# imsensor-esp-v01.net
KiCad netlist of a schematic drawn in EAGLE
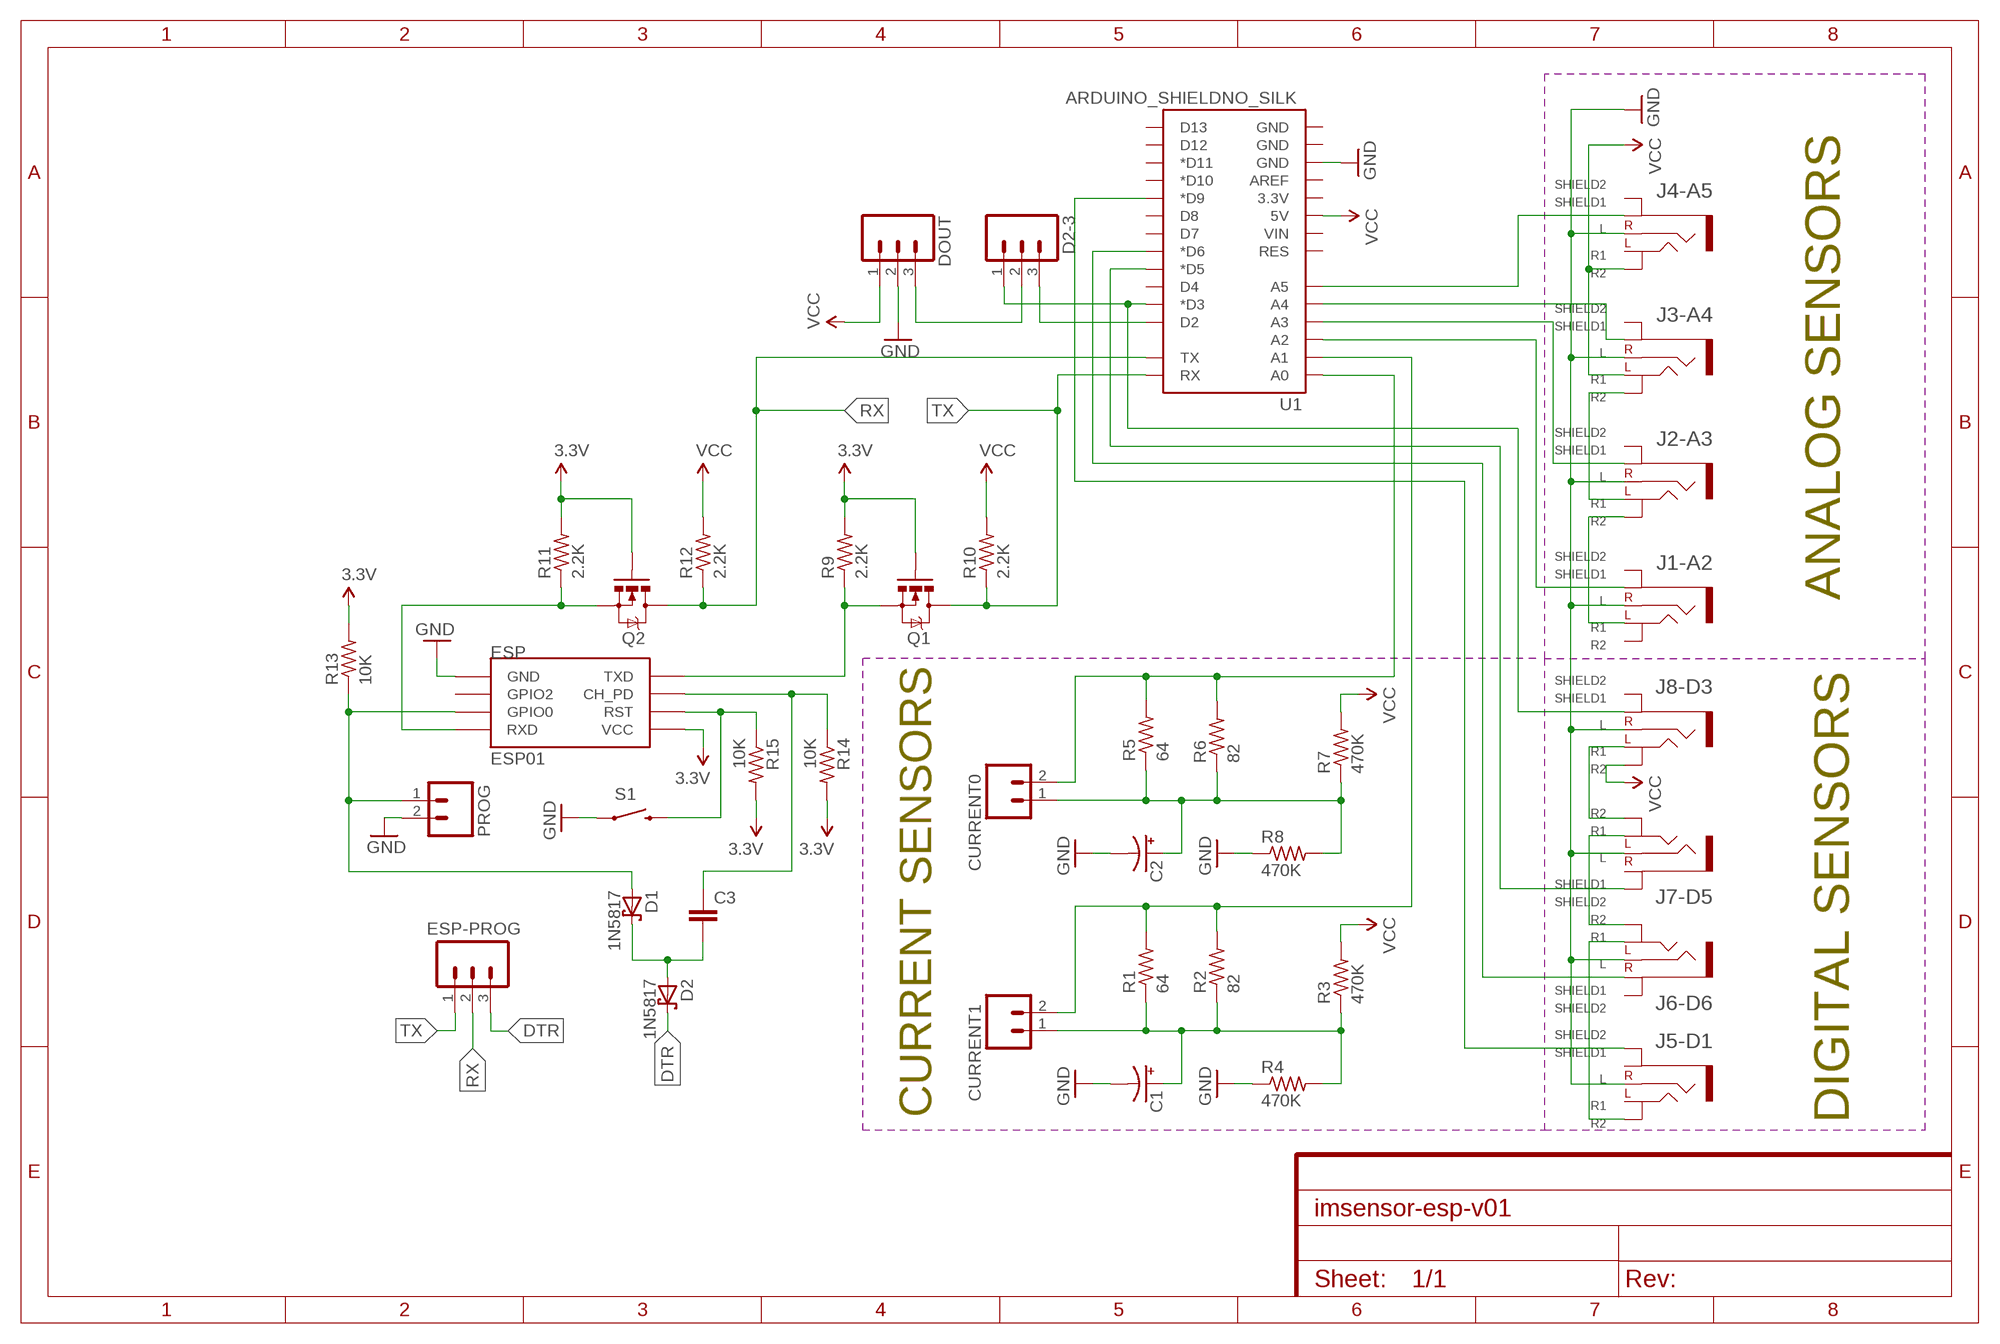
[diagram p0: schematic, sheet 1]

(export (version "E")
  (design (tool "Eeschema 10.0.6"))
  (components
    (comp (ref "C1")
      (value "10UF-25V-20%(PTH)")
      (footprint "eagle-import:CPOL-RADIAL-10UF-25V")
      (libsource (lib "eagle-import") (part "10UF-25V-20%(PTH)"))
    )
    (comp (ref "C2")
      (value "10UF-25V-20%(PTH)")
      (footprint "eagle-import:CPOL-RADIAL-10UF-25V")
      (libsource (lib "eagle-import") (part "10UF-25V-20%(PTH)"))
    )
    (comp (ref "C3")
      (value "CAPPTH")
      (footprint "eagle-import:CAP-PTH-SMALL")
      (libsource (lib "eagle-import") (part "CAPPTH"))
    )
    (comp (ref "CURRENT0")
      (value "M02PTH")
      (footprint "eagle-import:1X02")
      (libsource (lib "eagle-import") (part "M02PTH"))
    )
    (comp (ref "CURRENT1")
      (value "M02PTH")
      (footprint "eagle-import:1X02")
      (libsource (lib "eagle-import") (part "M02PTH"))
    )
    (comp (ref "D1")
      (value "1N5817")
      (footprint "eagle-import:DO35-7")
      (libsource (lib "eagle-import") (part "SCHOTTKY-DIODEDO35-7"))
    )
    (comp (ref "D2")
      (value "1N5817")
      (footprint "eagle-import:DO35-7")
      (libsource (lib "eagle-import") (part "SCHOTTKY-DIODEDO35-7"))
    )
    (comp (ref "D2-3")
      (value "M03PTH")
      (footprint "eagle-import:1X03")
      (libsource (lib "eagle-import") (part "M03PTH"))
    )
    (comp (ref "DOUT")
      (value "M03PTH")
      (footprint "eagle-import:1X03")
      (libsource (lib "eagle-import") (part "M03PTH"))
    )
    (comp (ref "ESP")
      (value "ESP01")
      (footprint "eagle-import:ESP01")
      (libsource (lib "eagle-import") (part "ESP01"))
    )
    (comp (ref "ESP-PROG")
      (value "M03PTH")
      (footprint "eagle-import:1X03")
      (libsource (lib "eagle-import") (part "M03PTH"))
    )
    (comp (ref "J1-A2")
      (value "PJ-313-SPAD")
      (footprint "eagle-import:PJ-313-5PIN-SMALL")
      (libsource (lib "eagle-import") (part "PJ-313-SPAD"))
    )
    (comp (ref "J2-A3")
      (value "PJ-313-SPAD")
      (footprint "eagle-import:PJ-313-5PIN-SMALL")
      (libsource (lib "eagle-import") (part "PJ-313-SPAD"))
    )
    (comp (ref "J3-A4")
      (value "PJ-313-SPAD")
      (footprint "eagle-import:PJ-313-5PIN-SMALL")
      (libsource (lib "eagle-import") (part "PJ-313-SPAD"))
    )
    (comp (ref "J4-A5")
      (value "PJ-313-SPAD")
      (footprint "eagle-import:PJ-313-5PIN-SMALL")
      (libsource (lib "eagle-import") (part "PJ-313-SPAD"))
    )
    (comp (ref "J5-D1")
      (value "PJ-313-SPAD")
      (footprint "eagle-import:PJ-313-5PIN-SMALL")
      (libsource (lib "eagle-import") (part "PJ-313-SPAD"))
    )
    (comp (ref "J6-D6")
      (value "PJ-313-SPAD")
      (footprint "eagle-import:PJ-313-5PIN-SMALL")
      (libsource (lib "eagle-import") (part "PJ-313-SPAD"))
    )
    (comp (ref "J7-D5")
      (value "PJ-313-SPAD")
      (footprint "eagle-import:PJ-313-5PIN-SMALL")
      (libsource (lib "eagle-import") (part "PJ-313-SPAD"))
    )
    (comp (ref "J8-D3")
      (value "PJ-313-SPAD")
      (footprint "eagle-import:PJ-313-5PIN-SMALL")
      (libsource (lib "eagle-import") (part "PJ-313-SPAD"))
    )
    (comp (ref "PROG")
      (value "M02PTH")
      (footprint "eagle-import:1X02")
      (libsource (lib "eagle-import") (part "M02PTH"))
    )
    (comp (ref "Q1")
      (value "MOSFET-NCHANNEL2N7000")
      (footprint "eagle-import:TO-92")
      (libsource (lib "eagle-import") (part "MOSFET-NCHANNEL2N7000"))
    )
    (comp (ref "Q2")
      (value "MOSFET-NCHANNEL2N7000")
      (footprint "eagle-import:TO-92")
      (libsource (lib "eagle-import") (part "MOSFET-NCHANNEL2N7000"))
    )
    (comp (ref "R1")
      (value "64")
      (footprint "eagle-import:0207_10")
      (libsource (lib "eagle-import") (part "R-US_0207/10"))
    )
    (comp (ref "R2")
      (value "82")
      (footprint "eagle-import:0207_10")
      (libsource (lib "eagle-import") (part "R-US_0207/10"))
    )
    (comp (ref "R3")
      (value "470K")
      (footprint "eagle-import:0207_10")
      (libsource (lib "eagle-import") (part "R-US_0207/10"))
    )
    (comp (ref "R4")
      (value "470K")
      (footprint "eagle-import:0207_10")
      (libsource (lib "eagle-import") (part "R-US_0207/10"))
    )
    (comp (ref "R5")
      (value "64")
      (footprint "eagle-import:0207_10")
      (libsource (lib "eagle-import") (part "R-US_0207/10"))
    )
    (comp (ref "R6")
      (value "82")
      (footprint "eagle-import:0207_10")
      (libsource (lib "eagle-import") (part "R-US_0207/10"))
    )
    (comp (ref "R7")
      (value "470K")
      (footprint "eagle-import:0207_10")
      (libsource (lib "eagle-import") (part "R-US_0207/10"))
    )
    (comp (ref "R8")
      (value "470K")
      (footprint "eagle-import:0207_10")
      (libsource (lib "eagle-import") (part "R-US_0207/10"))
    )
    (comp (ref "R9")
      (value "2.2K")
      (footprint "eagle-import:0207_10")
      (libsource (lib "eagle-import") (part "R-US_0207/10"))
    )
    (comp (ref "R10")
      (value "2.2K")
      (footprint "eagle-import:0207_10")
      (libsource (lib "eagle-import") (part "R-US_0207/10"))
    )
    (comp (ref "R11")
      (value "2.2K")
      (footprint "eagle-import:0207_10")
      (libsource (lib "eagle-import") (part "R-US_0207/10"))
    )
    (comp (ref "R12")
      (value "2.2K")
      (footprint "eagle-import:0207_10")
      (libsource (lib "eagle-import") (part "R-US_0207/10"))
    )
    (comp (ref "R13")
      (value "10K")
      (footprint "eagle-import:0207_10")
      (libsource (lib "eagle-import") (part "R-US_0207/10"))
    )
    (comp (ref "R14")
      (value "10K")
      (footprint "eagle-import:0207_10")
      (libsource (lib "eagle-import") (part "R-US_0207/10"))
    )
    (comp (ref "R15")
      (value "10K")
      (footprint "eagle-import:0207_10")
      (libsource (lib "eagle-import") (part "R-US_0207/10"))
    )
    (comp (ref "S1")
      (value "SWITCH-MOMENTARY-2PTH")
      (footprint "eagle-import:TACTILE-PTH")
      (libsource (lib "eagle-import") (part "SWITCH-MOMENTARY-2PTH"))
    )
    (comp (ref "U1")
      (value "ARDUINO_SHIELDNO_SILK")
      (footprint "eagle-import:DUEMILANOVE_VIAS")
      (libsource (lib "eagle-import") (part "ARDUINO_SHIELDNO_SILK"))
    )
  )
  (nets
    (net (code "1") (name "3.3V") (class "Default")
      (node (ref "ESP") (pin "VCC") (pinfunction "VCC_VCC") (pintype "bidirectional"))
      (node (ref "Q1") (pin "2") (pinfunction "G_2") (pintype "passive"))
      (node (ref "Q2") (pin "2") (pinfunction "G_2") (pintype "passive"))
      (node (ref "R11") (pin "2") (pinfunction "2_2") (pintype "passive"))
      (node (ref "R13") (pin "2") (pinfunction "2_2") (pintype "passive"))
      (node (ref "R14") (pin "2") (pinfunction "2_2") (pintype "passive"))
      (node (ref "R15") (pin "2") (pinfunction "2_2") (pintype "passive"))
      (node (ref "R9") (pin "2") (pinfunction "2_2") (pintype "passive"))
    )
    (net (code "2") (name "DTR") (class "Default")
      (node (ref "D2") (pin "C") (pinfunction "C_C") (pintype "passive"))
      (node (ref "ESP-PROG") (pin "3") (pinfunction "3_3") (pintype "passive"))
    )
    (net (code "3") (name "GND") (class "Default")
      (node (ref "C1") (pin "2") (pinfunction "-_2") (pintype "passive"))
      (node (ref "C2") (pin "2") (pinfunction "-_2") (pintype "passive"))
      (node (ref "DOUT") (pin "2") (pinfunction "2_2") (pintype "passive"))
      (node (ref "ESP") (pin "GND") (pinfunction "GND_GND") (pintype "bidirectional"))
      (node (ref "J1-A2") (pin "2") (pinfunction "R_2") (pintype "bidirectional"))
      (node (ref "J2-A3") (pin "2") (pinfunction "R_2") (pintype "bidirectional"))
      (node (ref "J3-A4") (pin "2") (pinfunction "R_2") (pintype "bidirectional"))
      (node (ref "J4-A5") (pin "2") (pinfunction "R_2") (pintype "bidirectional"))
      (node (ref "J5-D1") (pin "2") (pinfunction "R_2") (pintype "bidirectional"))
      (node (ref "J6-D6") (pin "2") (pinfunction "R_2") (pintype "bidirectional"))
      (node (ref "J7-D5") (pin "2") (pinfunction "R_2") (pintype "bidirectional"))
      (node (ref "J8-D3") (pin "2") (pinfunction "R_2") (pintype "bidirectional"))
      (node (ref "PROG") (pin "2") (pinfunction "2_2") (pintype "passive"))
      (node (ref "R4") (pin "1") (pinfunction "1_1") (pintype "passive"))
      (node (ref "R8") (pin "1") (pinfunction "1_1") (pintype "passive"))
      (node (ref "S1") (pin "1") (pinfunction "1_1") (pintype "passive"))
      (node (ref "U1") (pin "GND@2") (pinfunction "GND_GND@2") (pintype "bidirectional"))
    )
    (net (code "4") (name "Net-(C1-+)") (class "Default")
      (node (ref "C1") (pin "1") (pinfunction "+_1") (pintype "passive"))
      (node (ref "CURRENT1") (pin "1") (pinfunction "1_1") (pintype "passive"))
      (node (ref "R1") (pin "1") (pinfunction "1_1") (pintype "passive"))
      (node (ref "R2") (pin "1") (pinfunction "1_1") (pintype "passive"))
      (node (ref "R3") (pin "1") (pinfunction "1_1") (pintype "passive"))
      (node (ref "R4") (pin "2") (pinfunction "2_2") (pintype "passive"))
    )
    (net (code "5") (name "Net-(C2-+)") (class "Default")
      (node (ref "C2") (pin "1") (pinfunction "+_1") (pintype "passive"))
      (node (ref "CURRENT0") (pin "1") (pinfunction "1_1") (pintype "passive"))
      (node (ref "R5") (pin "1") (pinfunction "1_1") (pintype "passive"))
      (node (ref "R6") (pin "1") (pinfunction "1_1") (pintype "passive"))
      (node (ref "R7") (pin "1") (pinfunction "1_1") (pintype "passive"))
      (node (ref "R8") (pin "2") (pinfunction "2_2") (pintype "passive"))
    )
    (net (code "6") (name "Net-(C3-Pad1)") (class "Default")
      (node (ref "C3") (pin "1") (pinfunction "1_1") (pintype "passive"))
      (node (ref "ESP") (pin "CH_PD") (pinfunction "CH_PD_CH_PD") (pintype "bidirectional"))
      (node (ref "R14") (pin "1") (pinfunction "1_1") (pintype "passive"))
    )
    (net (code "7") (name "Net-(C3-Pad2)") (class "Default")
      (node (ref "C3") (pin "2") (pinfunction "2_2") (pintype "passive"))
      (node (ref "D1") (pin "C") (pinfunction "C_C") (pintype "passive"))
      (node (ref "D2") (pin "A") (pinfunction "A_A") (pintype "passive"))
    )
    (net (code "8") (name "Net-(CURRENT0-Pad2)") (class "Default")
      (node (ref "CURRENT0") (pin "2") (pinfunction "2_2") (pintype "passive"))
      (node (ref "R5") (pin "2") (pinfunction "2_2") (pintype "passive"))
      (node (ref "R6") (pin "2") (pinfunction "2_2") (pintype "passive"))
      (node (ref "U1") (pin "A0") (pinfunction "A0_A0") (pintype "bidirectional"))
    )
    (net (code "9") (name "Net-(CURRENT1-Pad2)") (class "Default")
      (node (ref "CURRENT1") (pin "2") (pinfunction "2_2") (pintype "passive"))
      (node (ref "R1") (pin "2") (pinfunction "2_2") (pintype "passive"))
      (node (ref "R2") (pin "2") (pinfunction "2_2") (pintype "passive"))
      (node (ref "U1") (pin "A1") (pinfunction "A1_A1") (pintype "bidirectional"))
    )
    (net (code "10") (name "Net-(D1-PadA)") (class "Default")
      (node (ref "D1") (pin "A") (pinfunction "A_A") (pintype "passive"))
      (node (ref "ESP") (pin "GPIO0") (pinfunction "GPIO0_GPIO0") (pintype "bidirectional"))
      (node (ref "PROG") (pin "1") (pinfunction "1_1") (pintype "passive"))
      (node (ref "R13") (pin "1") (pinfunction "1_1") (pintype "passive"))
    )
    (net (code "11") (name "Net-(D2-3-Pad2)") (class "Default")
      (node (ref "D2-3") (pin "2") (pinfunction "2_2") (pintype "passive"))
      (node (ref "DOUT") (pin "3") (pinfunction "3_3") (pintype "passive"))
    )
    (net (code "12") (name "Net-(D2-3-Pad3)") (class "Default")
      (node (ref "D2-3") (pin "3") (pinfunction "3_3") (pintype "passive"))
      (node (ref "U1") (pin "D2") (pinfunction "D2_D2") (pintype "bidirectional"))
    )
    (net (code "13") (name "Net-(ESP-RXD)") (class "Default")
      (node (ref "ESP") (pin "RX") (pinfunction "RXD_RX") (pintype "bidirectional"))
      (node (ref "Q2") (pin "1") (pinfunction "S_1") (pintype "passive"))
      (node (ref "R11") (pin "1") (pinfunction "1_1") (pintype "passive"))
    )
    (net (code "14") (name "Net-(ESP-TXD)") (class "Default")
      (node (ref "ESP") (pin "TX") (pinfunction "TXD_TX") (pintype "bidirectional"))
      (node (ref "Q1") (pin "1") (pinfunction "S_1") (pintype "passive"))
      (node (ref "R9") (pin "1") (pinfunction "1_1") (pintype "passive"))
    )
    (net (code "15") (name "Net-(J1-A2-L1)") (class "Default")
      (node (ref "J1-A2") (pin "3.1") (pinfunction "L1_3.1") (pintype "bidirectional"))
      (node (ref "J2-A3") (pin "3.2") (pinfunction "L2_3.2") (pintype "bidirectional"))
    )
    (net (code "16") (name "Net-(J1-A2-SHIELD1)") (class "Default")
      (node (ref "J1-A2") (pin "1.1") (pinfunction "SHIELD1_1.1") (pintype "bidirectional"))
      (node (ref "U1") (pin "A2") (pinfunction "A2_A2") (pintype "bidirectional"))
    )
    (net (code "17") (name "Net-(J2-A3-L1)") (class "Default")
      (node (ref "J2-A3") (pin "3.1") (pinfunction "L1_3.1") (pintype "bidirectional"))
      (node (ref "J3-A4") (pin "3.2") (pinfunction "L2_3.2") (pintype "bidirectional"))
    )
    (net (code "18") (name "Net-(J2-A3-SHIELD1)") (class "Default")
      (node (ref "J2-A3") (pin "1.1") (pinfunction "SHIELD1_1.1") (pintype "bidirectional"))
      (node (ref "U1") (pin "A3") (pinfunction "A3_A3") (pintype "bidirectional"))
    )
    (net (code "19") (name "Net-(J3-A4-SHIELD1)") (class "Default")
      (node (ref "J3-A4") (pin "1.1") (pinfunction "SHIELD1_1.1") (pintype "bidirectional"))
      (node (ref "U1") (pin "A4") (pinfunction "A4_A4") (pintype "bidirectional"))
    )
    (net (code "20") (name "Net-(J4-A5-SHIELD1)") (class "Default")
      (node (ref "J4-A5") (pin "1.1") (pinfunction "SHIELD1_1.1") (pintype "bidirectional"))
      (node (ref "U1") (pin "A5") (pinfunction "A5_A5") (pintype "bidirectional"))
    )
    (net (code "21") (name "Net-(J5-D1-L2)") (class "Default")
      (node (ref "J5-D1") (pin "3.2") (pinfunction "L2_3.2") (pintype "bidirectional"))
      (node (ref "J6-D6") (pin "3.1") (pinfunction "L1_3.1") (pintype "bidirectional"))
    )
    (net (code "22") (name "Net-(J5-D1-SHIELD2)") (class "Default")
      (node (ref "J5-D1") (pin "1.2") (pinfunction "SHIELD2_1.2") (pintype "bidirectional"))
      (node (ref "U1") (pin "D9") (pinfunction "*D9_D9") (pintype "bidirectional"))
    )
    (net (code "23") (name "Net-(J6-D6-L2)") (class "Default")
      (node (ref "J6-D6") (pin "3.2") (pinfunction "L2_3.2") (pintype "bidirectional"))
      (node (ref "J7-D5") (pin "3.1") (pinfunction "L1_3.1") (pintype "bidirectional"))
    )
    (net (code "24") (name "Net-(J6-D6-SHIELD1)") (class "Default")
      (node (ref "J6-D6") (pin "1.1") (pinfunction "SHIELD1_1.1") (pintype "bidirectional"))
      (node (ref "U1") (pin "D6") (pinfunction "*D6_D6") (pintype "bidirectional"))
    )
    (net (code "25") (name "Net-(J7-D5-L2)") (class "Default")
      (node (ref "J7-D5") (pin "3.2") (pinfunction "L2_3.2") (pintype "bidirectional"))
      (node (ref "J8-D3") (pin "3.1") (pinfunction "L1_3.1") (pintype "bidirectional"))
    )
    (net (code "26") (name "Net-(J7-D5-SHIELD2)") (class "Default")
      (node (ref "J7-D5") (pin "1.2") (pinfunction "SHIELD2_1.2") (pintype "bidirectional"))
      (node (ref "U1") (pin "D5") (pinfunction "*D5_D5") (pintype "bidirectional"))
    )
    (net (code "27") (name "Net-(J8-D3-SHIELD1)") (class "Default")
      (node (ref "D2-3") (pin "1") (pinfunction "1_1") (pintype "passive"))
      (node (ref "J8-D3") (pin "1.1") (pinfunction "SHIELD1_1.1") (pintype "bidirectional"))
      (node (ref "U1") (pin "D3") (pinfunction "*D3_D3") (pintype "bidirectional"))
    )
    (net (code "28") (name "Net-(S1-2)") (class "Default")
      (node (ref "ESP") (pin "RST") (pinfunction "RST_RST") (pintype "bidirectional"))
      (node (ref "R15") (pin "1") (pinfunction "1_1") (pintype "passive"))
      (node (ref "S1") (pin "3") (pinfunction "2_3") (pintype "passive"))
    )
    (net (code "29") (name "RX") (class "Default")
      (node (ref "ESP-PROG") (pin "2") (pinfunction "2_2") (pintype "passive"))
      (node (ref "Q2") (pin "3") (pinfunction "D_3") (pintype "passive"))
      (node (ref "R12") (pin "1") (pinfunction "1_1") (pintype "passive"))
      (node (ref "U1") (pin "TX") (pinfunction "TX_TX") (pintype "bidirectional"))
    )
    (net (code "30") (name "TX") (class "Default")
      (node (ref "ESP-PROG") (pin "1") (pinfunction "1_1") (pintype "passive"))
      (node (ref "Q1") (pin "3") (pinfunction "D_3") (pintype "passive"))
      (node (ref "R10") (pin "1") (pinfunction "1_1") (pintype "passive"))
      (node (ref "U1") (pin "RX") (pinfunction "RX_RX") (pintype "bidirectional"))
    )
    (net (code "31") (name "VCC") (class "Default")
      (node (ref "DOUT") (pin "1") (pinfunction "1_1") (pintype "passive"))
      (node (ref "J3-A4") (pin "3.1") (pinfunction "L1_3.1") (pintype "bidirectional"))
      (node (ref "J4-A5") (pin "3.2") (pinfunction "L2_3.2") (pintype "bidirectional"))
      (node (ref "J8-D3") (pin "3.2") (pinfunction "L2_3.2") (pintype "bidirectional"))
      (node (ref "R10") (pin "2") (pinfunction "2_2") (pintype "passive"))
      (node (ref "R12") (pin "2") (pinfunction "2_2") (pintype "passive"))
      (node (ref "R3") (pin "2") (pinfunction "2_2") (pintype "passive"))
      (node (ref "R7") (pin "2") (pinfunction "2_2") (pintype "passive"))
      (node (ref "U1") (pin "5V") (pinfunction "5V_5V") (pintype "bidirectional"))
    )
    (net (code "32") (name "unconnected-(ESP-PadGPIO2)") (class "Default")
      (node (ref "ESP") (pin "GPIO2") (pinfunction "GPIO2_GPIO2") (pintype "bidirectional"))
    )
    (net (code "33") (name "unconnected-(J1-A2-L2-Pad3.2)") (class "Default")
      (node (ref "J1-A2") (pin "3.2") (pinfunction "L2_3.2") (pintype "bidirectional"))
    )
    (net (code "34") (name "unconnected-(J1-A2-SHIELD2-Pad1.2)") (class "Default")
      (node (ref "J1-A2") (pin "1.2") (pinfunction "SHIELD2_1.2") (pintype "bidirectional"))
    )
    (net (code "35") (name "unconnected-(J2-A3-SHIELD2-Pad1.2)") (class "Default")
      (node (ref "J2-A3") (pin "1.2") (pinfunction "SHIELD2_1.2") (pintype "bidirectional"))
    )
    (net (code "36") (name "unconnected-(J3-A4-SHIELD2-Pad1.2)") (class "Default")
      (node (ref "J3-A4") (pin "1.2") (pinfunction "SHIELD2_1.2") (pintype "bidirectional"))
    )
    (net (code "37") (name "unconnected-(J4-A5-L1-Pad3.1)") (class "Default")
      (node (ref "J4-A5") (pin "3.1") (pinfunction "L1_3.1") (pintype "bidirectional"))
    )
    (net (code "38") (name "unconnected-(J4-A5-SHIELD2-Pad1.2)") (class "Default")
      (node (ref "J4-A5") (pin "1.2") (pinfunction "SHIELD2_1.2") (pintype "bidirectional"))
    )
    (net (code "39") (name "unconnected-(J5-D1-L1-Pad3.1)") (class "Default")
      (node (ref "J5-D1") (pin "3.1") (pinfunction "L1_3.1") (pintype "bidirectional"))
    )
    (net (code "40") (name "unconnected-(J5-D1-SHIELD1-Pad1.1)") (class "Default")
      (node (ref "J5-D1") (pin "1.1") (pinfunction "SHIELD1_1.1") (pintype "bidirectional"))
    )
    (net (code "41") (name "unconnected-(J6-D6-SHIELD2-Pad1.2)") (class "Default")
      (node (ref "J6-D6") (pin "1.2") (pinfunction "SHIELD2_1.2") (pintype "bidirectional"))
    )
    (net (code "42") (name "unconnected-(J7-D5-SHIELD1-Pad1.1)") (class "Default")
      (node (ref "J7-D5") (pin "1.1") (pinfunction "SHIELD1_1.1") (pintype "bidirectional"))
    )
    (net (code "43") (name "unconnected-(J8-D3-SHIELD2-Pad1.2)") (class "Default")
      (node (ref "J8-D3") (pin "1.2") (pinfunction "SHIELD2_1.2") (pintype "bidirectional"))
    )
    (net (code "44") (name "unconnected-(U1-*D10-PadD10)") (class "Default")
      (node (ref "U1") (pin "D10") (pinfunction "*D10_D10") (pintype "bidirectional"))
    )
    (net (code "45") (name "unconnected-(U1-*D11-PadD11)") (class "Default")
      (node (ref "U1") (pin "D11") (pinfunction "*D11_D11") (pintype "bidirectional"))
    )
    (net (code "46") (name "unconnected-(U1-GND-PadGND@0)") (class "Default")
      (node (ref "U1") (pin "GND@0") (pinfunction "GND_GND@0") (pintype "bidirectional"))
    )
    (net (code "47") (name "unconnected-(U1-GND-PadGND@1)") (class "Default")
      (node (ref "U1") (pin "GND@1") (pinfunction "GND_GND@1") (pintype "bidirectional"))
    )
    (net (code "48") (name "unconnected-(U1-Pad3.3V)") (class "Default")
      (node (ref "U1") (pin "3.3V") (pinfunction "3.3V_3.3V") (pintype "bidirectional"))
    )
    (net (code "49") (name "unconnected-(U1-PadAREF)") (class "Default")
      (node (ref "U1") (pin "AREF") (pinfunction "AREF_AREF") (pintype "bidirectional"))
    )
    (net (code "50") (name "unconnected-(U1-PadD4)") (class "Default")
      (node (ref "U1") (pin "D4") (pinfunction "D4_D4") (pintype "bidirectional"))
    )
    (net (code "51") (name "unconnected-(U1-PadD7)") (class "Default")
      (node (ref "U1") (pin "D7") (pinfunction "D7_D7") (pintype "bidirectional"))
    )
    (net (code "52") (name "unconnected-(U1-PadD8)") (class "Default")
      (node (ref "U1") (pin "D8") (pinfunction "D8_D8") (pintype "bidirectional"))
    )
    (net (code "53") (name "unconnected-(U1-PadD12)") (class "Default")
      (node (ref "U1") (pin "D12") (pinfunction "D12_D12") (pintype "bidirectional"))
    )
    (net (code "54") (name "unconnected-(U1-PadD13)") (class "Default")
      (node (ref "U1") (pin "D13") (pinfunction "D13_D13") (pintype "bidirectional"))
    )
    (net (code "55") (name "unconnected-(U1-PadRES)") (class "Default")
      (node (ref "U1") (pin "RES") (pinfunction "RES_RES") (pintype "bidirectional"))
    )
    (net (code "56") (name "unconnected-(U1-PadVIN)") (class "Default")
      (node (ref "U1") (pin "VIN") (pinfunction "VIN_VIN") (pintype "bidirectional"))
    )
  )
)
